# USI-WM-BN-BM-22-v1_0_0.net
KiCad netlist of a schematic drawn in EAGLE
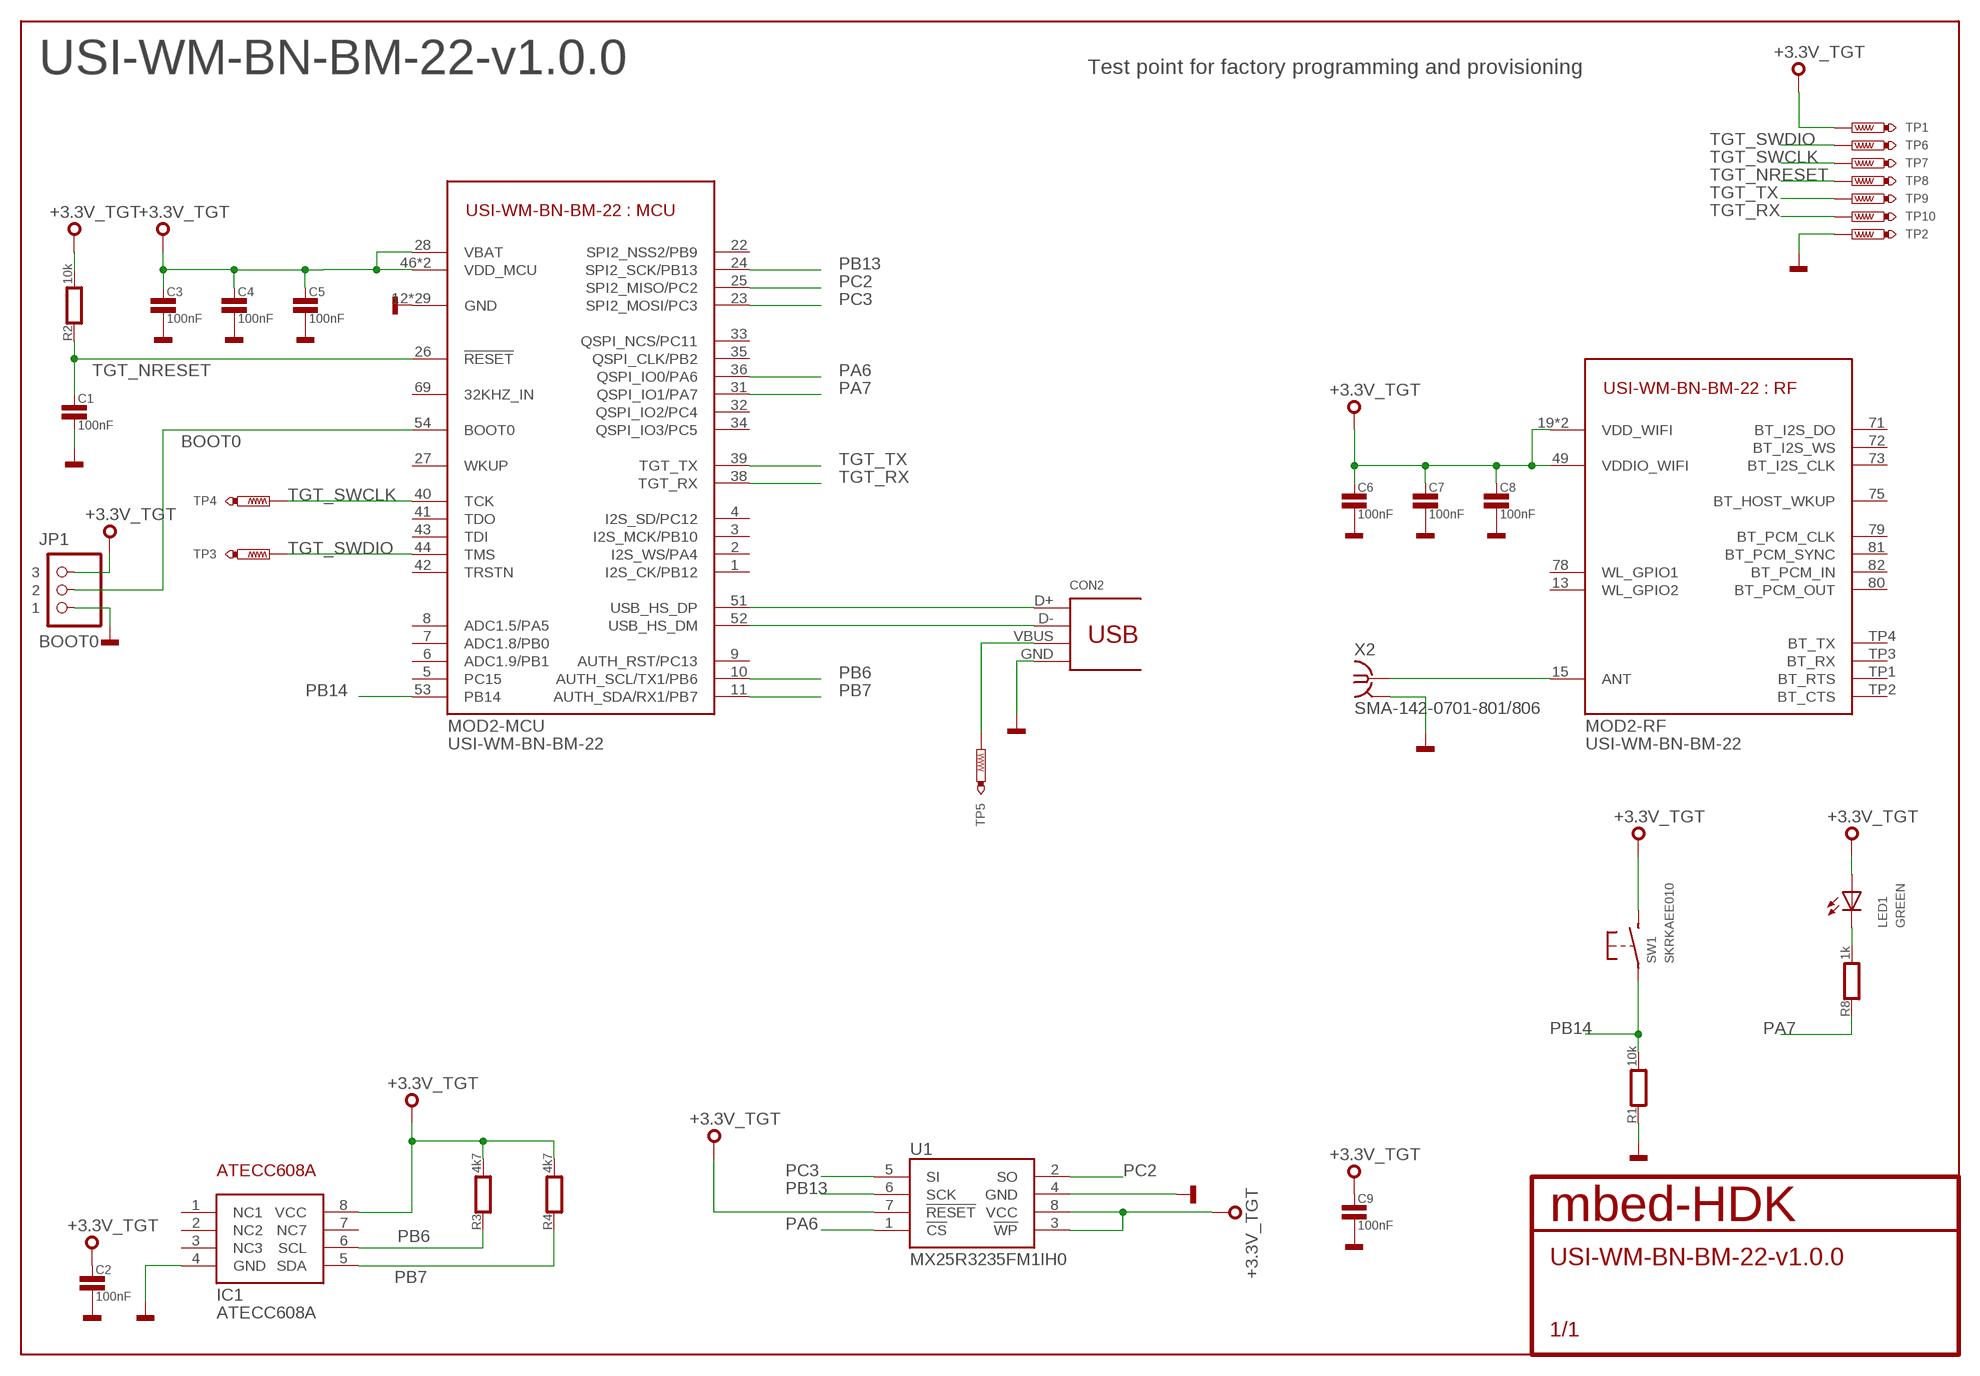
[diagram p0: schematic, sheet 1]

(export (version "E")
  (design (tool "Eeschema 10.0.6"))
  (components
    (comp (ref "C1")
      (value "100nF")
      (footprint "eagle-import:0603")
      (libsource (lib "eagle-import") (part "C0603"))
    )
    (comp (ref "C2")
      (value "100nF")
      (footprint "eagle-import:0603")
      (libsource (lib "eagle-import") (part "C0603"))
    )
    (comp (ref "C3")
      (value "100nF")
      (footprint "eagle-import:0603")
      (libsource (lib "eagle-import") (part "C0603"))
    )
    (comp (ref "C4")
      (value "100nF")
      (footprint "eagle-import:0603")
      (libsource (lib "eagle-import") (part "C0603"))
    )
    (comp (ref "C5")
      (value "100nF")
      (footprint "eagle-import:0603")
      (libsource (lib "eagle-import") (part "C0603"))
    )
    (comp (ref "C6")
      (value "100nF")
      (footprint "eagle-import:0603")
      (libsource (lib "eagle-import") (part "C0603"))
    )
    (comp (ref "C7")
      (value "100nF")
      (footprint "eagle-import:0603")
      (libsource (lib "eagle-import") (part "C0603"))
    )
    (comp (ref "C8")
      (value "100nF")
      (footprint "eagle-import:0603")
      (libsource (lib "eagle-import") (part "C0603"))
    )
    (comp (ref "C9")
      (value "100nF")
      (footprint "eagle-import:0603")
      (libsource (lib "eagle-import") (part "C0603"))
    )
    (comp (ref "CON2")
      (value "47346-0001")
      (footprint "eagle-import:USB-MICRO-B-H")
      (fields (field (name "MF") "MOLEX"))
      (libsource (lib "eagle-import") (part "47346-0001"))
    )
    (comp (ref "IC1")
      (value "ATECC608A")
      (footprint "eagle-import:SO8")
      (fields (field (name "MF") "Atmel"))
      (libsource (lib "eagle-import") (part "ATECC608A"))
    )
    (comp (ref "JP1")
      (value "BOOT0")
      (footprint "eagle-import:1X03")
      (libsource (lib "eagle-import") (part "PINHD-1X3"))
    )
    (comp (ref "LED1")
      (value "GREEN")
      (footprint "eagle-import:CHIPLED_0603")
      (fields (field (name "MF") "Wurth Electronics Inc"))
      (libsource (lib "eagle-import") (part "SMD_LED0603"))
    )
    (comp (ref "MOD2")
      (value "USI-WM-BN-BM-22")
      (footprint "eagle-import:USI-WM-BN-BM-22")
      (libsource (lib "eagle-import") (part "USI-WM-BN-BM-22"))
    )
    (comp (ref "R1")
      (value "10k")
      (footprint "eagle-import:0603")
      (libsource (lib "eagle-import") (part "R0603"))
    )
    (comp (ref "R2")
      (value "10k")
      (footprint "eagle-import:0603")
      (libsource (lib "eagle-import") (part "R0603"))
    )
    (comp (ref "R3")
      (value "4k7")
      (footprint "eagle-import:0603")
      (libsource (lib "eagle-import") (part "R0603"))
    )
    (comp (ref "R4")
      (value "4k7")
      (footprint "eagle-import:0603")
      (libsource (lib "eagle-import") (part "R0603"))
    )
    (comp (ref "R8")
      (value "1k")
      (footprint "eagle-import:0603")
      (libsource (lib "eagle-import") (part "R0603"))
    )
    (comp (ref "SW1")
      (value "SKRKAEE010")
      (footprint "eagle-import:SKRKAEE010")
      (fields (field (name "MF") "ALPS"))
      (libsource (lib "eagle-import") (part "SKRKAEE010"))
    )
    (comp (ref "TP1")
      (value "TEST_POINT-50R-SMD")
      (footprint "eagle-import:TP50-SMD")
      (libsource (lib "eagle-import") (part "TEST_POINT-50R-SMD"))
    )
    (comp (ref "TP2")
      (value "TEST_POINT-50R-SMD")
      (footprint "eagle-import:TP50-SMD")
      (libsource (lib "eagle-import") (part "TEST_POINT-50R-SMD"))
    )
    (comp (ref "TP3")
      (value "TEST_POINT-50R-SMD")
      (footprint "eagle-import:TP50-SMD")
      (libsource (lib "eagle-import") (part "TEST_POINT-50R-SMD"))
    )
    (comp (ref "TP4")
      (value "TEST_POINT-50R-SMD")
      (footprint "eagle-import:TP50-SMD")
      (libsource (lib "eagle-import") (part "TEST_POINT-50R-SMD"))
    )
    (comp (ref "TP5")
      (value "TEST_POINT-50R-SMD")
      (footprint "eagle-import:TP50-SMD")
      (libsource (lib "eagle-import") (part "TEST_POINT-50R-SMD"))
    )
    (comp (ref "TP6")
      (value "TEST_POINT-50R-SMD")
      (footprint "eagle-import:TP50-SMD")
      (libsource (lib "eagle-import") (part "TEST_POINT-50R-SMD"))
    )
    (comp (ref "TP7")
      (value "TEST_POINT-50R-SMD")
      (footprint "eagle-import:TP50-SMD")
      (libsource (lib "eagle-import") (part "TEST_POINT-50R-SMD"))
    )
    (comp (ref "TP8")
      (value "TEST_POINT-50R-SMD")
      (footprint "eagle-import:TP50-SMD")
      (libsource (lib "eagle-import") (part "TEST_POINT-50R-SMD"))
    )
    (comp (ref "TP9")
      (value "TEST_POINT-50R-SMD")
      (footprint "eagle-import:TP50-SMD")
      (libsource (lib "eagle-import") (part "TEST_POINT-50R-SMD"))
    )
    (comp (ref "TP10")
      (value "TEST_POINT-50R-SMD")
      (footprint "eagle-import:TP50-SMD")
      (libsource (lib "eagle-import") (part "TEST_POINT-50R-SMD"))
    )
    (comp (ref "U1")
      (value "MX25R3235FM1IH0")
      (footprint "eagle-import:SO8")
      (fields (field (name "MF") "Macronix"))
      (libsource (lib "eagle-import") (part "MX25R3235FM1IH0"))
    )
    (comp (ref "X2")
      (value "SMA-142-0701-801/806")
      (footprint "eagle-import:J502-ND-142-0701-801_806")
      (fields (field (name "MF") "JOHNSON COMPONENTS") (field (name "MPN") "142-0701-801"))
      (libsource (lib "eagle-import") (part "SMA-142-0701-801/806"))
    )
  )
  (nets
    (net (code "1") (name "+3.3V_TGT") (class "Default")
      (node (ref "C2") (pin "1") (pinfunction "P$1_1") (pintype "passive"))
      (node (ref "C3") (pin "1") (pinfunction "P$1_1") (pintype "passive"))
      (node (ref "C4") (pin "1") (pinfunction "P$1_1") (pintype "passive"))
      (node (ref "C5") (pin "1") (pinfunction "P$1_1") (pintype "passive"))
      (node (ref "C6") (pin "1") (pinfunction "P$1_1") (pintype "passive"))
      (node (ref "C7") (pin "1") (pinfunction "P$1_1") (pintype "passive"))
      (node (ref "C8") (pin "1") (pinfunction "P$1_1") (pintype "passive"))
      (node (ref "C9") (pin "1") (pinfunction "P$1_1") (pintype "passive"))
      (node (ref "IC1") (pin "8") (pinfunction "VCC_8") (pintype "bidirectional"))
      (node (ref "JP1") (pin "3") (pinfunction "3_3") (pintype "passive"))
      (node (ref "LED1") (pin "A") (pinfunction "A_A") (pintype "passive"))
      (node (ref "MOD2") (pin "19") (pinfunction "VDD_WIFI_19") (pintype "bidirectional"))
      (node (ref "MOD2") (pin "20") (pinfunction "VDD_WIFI_20") (pintype "bidirectional"))
      (node (ref "MOD2") (pin "28") (pinfunction "VBAT_28") (pintype "bidirectional"))
      (node (ref "MOD2") (pin "46") (pinfunction "VDD_MCU_46") (pintype "bidirectional"))
      (node (ref "MOD2") (pin "47") (pinfunction "VDD_MCU_47") (pintype "bidirectional"))
      (node (ref "MOD2") (pin "49") (pinfunction "VDDIO_WIFI_49") (pintype "bidirectional"))
      (node (ref "R2") (pin "2") (pinfunction "P$2_2") (pintype "passive"))
      (node (ref "R3") (pin "2") (pinfunction "P$2_2") (pintype "passive"))
      (node (ref "R4") (pin "2") (pinfunction "P$2_2") (pintype "passive"))
      (node (ref "SW1") (pin "P$2") (pinfunction "S_P$2") (pintype "passive"))
      (node (ref "TP1") (pin "TP") (pinfunction "TP_TP") (pintype "input"))
      (node (ref "U1") (pin "3") (pinfunction "~{WP}_3") (pintype "bidirectional"))
      (node (ref "U1") (pin "7") (pinfunction "~{RESET}_7") (pintype "bidirectional"))
      (node (ref "U1") (pin "8") (pinfunction "VCC_8") (pintype "bidirectional"))
    )
    (net (code "2") (name "/BOOT0") (class "Default")
      (node (ref "JP1") (pin "2") (pinfunction "2_2") (pintype "passive"))
      (node (ref "MOD2") (pin "54") (pinfunction "BOOT0_54") (pintype "bidirectional"))
    )
    (net (code "3") (name "/PA6") (class "Default")
      (node (ref "MOD2") (pin "36") (pinfunction "QSPI_IO0/PA6_36") (pintype "bidirectional"))
      (node (ref "U1") (pin "1") (pinfunction "~{CS}_1") (pintype "bidirectional"))
    )
    (net (code "4") (name "/PA7") (class "Default")
      (node (ref "MOD2") (pin "31") (pinfunction "QSPI_IO1/PA7_31") (pintype "bidirectional"))
      (node (ref "R8") (pin "1") (pinfunction "P$1_1") (pintype "passive"))
    )
    (net (code "5") (name "/PB6") (class "Default")
      (node (ref "IC1") (pin "6") (pinfunction "SCL_6") (pintype "bidirectional"))
      (node (ref "MOD2") (pin "10") (pinfunction "AUTH_SCL/TX1/PB6_10") (pintype "bidirectional"))
      (node (ref "R3") (pin "1") (pinfunction "P$1_1") (pintype "passive"))
    )
    (net (code "6") (name "/PB7") (class "Default")
      (node (ref "IC1") (pin "5") (pinfunction "SDA_5") (pintype "bidirectional"))
      (node (ref "MOD2") (pin "11") (pinfunction "AUTH_SDA/RX1/PB7_11") (pintype "bidirectional"))
      (node (ref "R4") (pin "1") (pinfunction "P$1_1") (pintype "passive"))
    )
    (net (code "7") (name "/PB13") (class "Default")
      (node (ref "MOD2") (pin "24") (pinfunction "SPI2_SCK/PB13_24") (pintype "bidirectional"))
      (node (ref "U1") (pin "6") (pinfunction "SCK_6") (pintype "bidirectional"))
    )
    (net (code "8") (name "/PB14") (class "Default")
      (node (ref "MOD2") (pin "53") (pinfunction "PB14_53") (pintype "bidirectional"))
      (node (ref "R1") (pin "2") (pinfunction "P$2_2") (pintype "passive"))
      (node (ref "SW1") (pin "P$1") (pinfunction "P_P$1") (pintype "passive"))
    )
    (net (code "9") (name "/PC2") (class "Default")
      (node (ref "MOD2") (pin "25") (pinfunction "SPI2_MISO/PC2_25") (pintype "bidirectional"))
      (node (ref "U1") (pin "2") (pinfunction "SO_2") (pintype "bidirectional"))
    )
    (net (code "10") (name "/PC3") (class "Default")
      (node (ref "MOD2") (pin "23") (pinfunction "SPI2_MOSI/PC3_23") (pintype "bidirectional"))
      (node (ref "U1") (pin "5") (pinfunction "SI_5") (pintype "bidirectional"))
    )
    (net (code "11") (name "/TGT_NRESET") (class "Default")
      (node (ref "C1") (pin "1") (pinfunction "P$1_1") (pintype "passive"))
      (node (ref "MOD2") (pin "26") (pinfunction "~{RESET}_26") (pintype "bidirectional"))
      (node (ref "R2") (pin "1") (pinfunction "P$1_1") (pintype "passive"))
      (node (ref "TP8") (pin "TP") (pinfunction "TP_TP") (pintype "input"))
    )
    (net (code "12") (name "/TGT_RX") (class "Default")
      (node (ref "MOD2") (pin "38") (pinfunction "TGT_RX_38") (pintype "bidirectional"))
      (node (ref "TP10") (pin "TP") (pinfunction "TP_TP") (pintype "input"))
    )
    (net (code "13") (name "/TGT_SWCLK") (class "Default")
      (node (ref "MOD2") (pin "40") (pinfunction "TCK_40") (pintype "bidirectional"))
      (node (ref "TP4") (pin "TP") (pinfunction "TP_TP") (pintype "input"))
      (node (ref "TP7") (pin "TP") (pinfunction "TP_TP") (pintype "input"))
    )
    (net (code "14") (name "/TGT_SWDIO") (class "Default")
      (node (ref "MOD2") (pin "44") (pinfunction "TMS_44") (pintype "bidirectional"))
      (node (ref "TP3") (pin "TP") (pinfunction "TP_TP") (pintype "input"))
      (node (ref "TP6") (pin "TP") (pinfunction "TP_TP") (pintype "input"))
    )
    (net (code "15") (name "/TGT_TX") (class "Default")
      (node (ref "MOD2") (pin "39") (pinfunction "TGT_TX_39") (pintype "bidirectional"))
      (node (ref "TP9") (pin "TP") (pinfunction "TP_TP") (pintype "input"))
    )
    (net (code "16") (name "GND") (class "Default")
      (node (ref "C1") (pin "2") (pinfunction "P$2_2") (pintype "passive"))
      (node (ref "C2") (pin "2") (pinfunction "P$2_2") (pintype "passive"))
      (node (ref "C3") (pin "2") (pinfunction "P$2_2") (pintype "passive"))
      (node (ref "C4") (pin "2") (pinfunction "P$2_2") (pintype "passive"))
      (node (ref "C5") (pin "2") (pinfunction "P$2_2") (pintype "passive"))
      (node (ref "C6") (pin "2") (pinfunction "P$2_2") (pintype "passive"))
      (node (ref "C7") (pin "2") (pinfunction "P$2_2") (pintype "passive"))
      (node (ref "C8") (pin "2") (pinfunction "P$2_2") (pintype "passive"))
      (node (ref "C9") (pin "2") (pinfunction "P$2_2") (pintype "passive"))
      (node (ref "CON2") (pin "GND") (pinfunction "GND_GND") (pintype "bidirectional"))
      (node (ref "IC1") (pin "4") (pinfunction "GND_4") (pintype "bidirectional"))
      (node (ref "JP1") (pin "1") (pinfunction "1_1") (pintype "passive"))
      (node (ref "MOD2") (pin "12") (pinfunction "GND_12") (pintype "bidirectional"))
      (node (ref "MOD2") (pin "14") (pinfunction "GND_14") (pintype "bidirectional"))
      (node (ref "MOD2") (pin "16") (pinfunction "GND_16") (pintype "bidirectional"))
      (node (ref "MOD2") (pin "17") (pinfunction "GND_17") (pintype "bidirectional"))
      (node (ref "MOD2") (pin "18") (pinfunction "GND_18") (pintype "bidirectional"))
      (node (ref "MOD2") (pin "21") (pinfunction "GND_21") (pintype "bidirectional"))
      (node (ref "MOD2") (pin "29") (pinfunction "GND_29") (pintype "bidirectional"))
      (node (ref "MOD2") (pin "30") (pinfunction "GND_30") (pintype "bidirectional"))
      (node (ref "MOD2") (pin "37") (pinfunction "GND_37") (pintype "bidirectional"))
      (node (ref "MOD2") (pin "45") (pinfunction "GND_45") (pintype "bidirectional"))
      (node (ref "MOD2") (pin "48") (pinfunction "GND_48") (pintype "bidirectional"))
      (node (ref "MOD2") (pin "50") (pinfunction "GND_50") (pintype "bidirectional"))
      (node (ref "MOD2") (pin "55") (pinfunction "GND_55") (pintype "bidirectional"))
      (node (ref "MOD2") (pin "56") (pinfunction "GND_56") (pintype "bidirectional"))
      (node (ref "MOD2") (pin "57") (pinfunction "GND_57") (pintype "bidirectional"))
      (node (ref "MOD2") (pin "58") (pinfunction "GND_58") (pintype "bidirectional"))
      (node (ref "MOD2") (pin "59") (pinfunction "GND_59") (pintype "bidirectional"))
      (node (ref "MOD2") (pin "60") (pinfunction "GND_60") (pintype "bidirectional"))
      (node (ref "MOD2") (pin "61") (pinfunction "GND_61") (pintype "bidirectional"))
      (node (ref "MOD2") (pin "62") (pinfunction "GND_62") (pintype "bidirectional"))
      (node (ref "MOD2") (pin "63") (pinfunction "GND_63") (pintype "bidirectional"))
      (node (ref "MOD2") (pin "64") (pinfunction "GND_64") (pintype "bidirectional"))
      (node (ref "MOD2") (pin "65") (pinfunction "GND_65") (pintype "bidirectional"))
      (node (ref "MOD2") (pin "66") (pinfunction "GND_66") (pintype "bidirectional"))
      (node (ref "MOD2") (pin "67") (pinfunction "GND_67") (pintype "bidirectional"))
      (node (ref "MOD2") (pin "68") (pinfunction "GND_68") (pintype "bidirectional"))
      (node (ref "MOD2") (pin "70") (pinfunction "GND_70") (pintype "bidirectional"))
      (node (ref "MOD2") (pin "74") (pinfunction "GND_74") (pintype "bidirectional"))
      (node (ref "MOD2") (pin "83") (pinfunction "GND_83") (pintype "bidirectional"))
      (node (ref "R1") (pin "1") (pinfunction "P$1_1") (pintype "passive"))
      (node (ref "TP2") (pin "TP") (pinfunction "TP_TP") (pintype "input"))
      (node (ref "U1") (pin "4") (pinfunction "GND_4") (pintype "bidirectional"))
      (node (ref "X2") (pin "G@1") (pinfunction "2_G@1") (pintype "passive"))
      (node (ref "X2") (pin "G@2") (pinfunction "2_G@2") (pintype "passive"))
      (node (ref "X2") (pin "G@3") (pinfunction "2_G@3") (pintype "passive"))
      (node (ref "X2") (pin "G@4") (pinfunction "2_G@4") (pintype "passive"))
    )
    (net (code "17") (name "Net-(CON2-PadVBUS)") (class "Default")
      (node (ref "CON2") (pin "VBUS") (pinfunction "VBUS_VBUS") (pintype "bidirectional"))
      (node (ref "TP5") (pin "TP") (pinfunction "TP_TP") (pintype "input"))
    )
    (net (code "18") (name "Net-(MOD2A-USB_HS_DM)") (class "Default")
      (node (ref "CON2") (pin "D-") (pinfunction "D-_D-") (pintype "bidirectional"))
      (node (ref "MOD2") (pin "52") (pinfunction "USB_HS_DM_52") (pintype "bidirectional"))
    )
    (net (code "19") (name "Net-(MOD2A-USB_HS_DP)") (class "Default")
      (node (ref "CON2") (pin "D+") (pinfunction "D+_D+") (pintype "bidirectional"))
      (node (ref "MOD2") (pin "51") (pinfunction "USB_HS_DP_51") (pintype "bidirectional"))
    )
    (net (code "20") (name "Net-(MOD2B-ANT)") (class "Default")
      (node (ref "MOD2") (pin "15") (pinfunction "ANT_15") (pintype "bidirectional"))
      (node (ref "X2") (pin "1") (pinfunction "1_1") (pintype "passive"))
    )
    (net (code "21") (name "Net-(R8-P$2)") (class "Default")
      (node (ref "LED1") (pin "C") (pinfunction "C_C") (pintype "passive"))
      (node (ref "R8") (pin "2") (pinfunction "P$2_2") (pintype "passive"))
    )
    (net (code "22") (name "unconnected-(IC1-NC1-Pad1)") (class "Default")
      (node (ref "IC1") (pin "1") (pinfunction "NC1_1") (pintype "bidirectional"))
    )
    (net (code "23") (name "unconnected-(IC1-NC2-Pad2)") (class "Default")
      (node (ref "IC1") (pin "2") (pinfunction "NC2_2") (pintype "bidirectional"))
    )
    (net (code "24") (name "unconnected-(IC1-NC3-Pad3)") (class "Default")
      (node (ref "IC1") (pin "3") (pinfunction "NC3_3") (pintype "bidirectional"))
    )
    (net (code "25") (name "unconnected-(IC1-NC7-Pad7)") (class "Default")
      (node (ref "IC1") (pin "7") (pinfunction "NC7_7") (pintype "bidirectional"))
    )
    (net (code "26") (name "unconnected-(MOD2A-32KHZ_IN-Pad69)") (class "Default")
      (node (ref "MOD2") (pin "69") (pinfunction "32KHZ_IN_69") (pintype "bidirectional"))
    )
    (net (code "27") (name "unconnected-(MOD2A-ADC1.5{slash}PA5-Pad8)") (class "Default")
      (node (ref "MOD2") (pin "8") (pinfunction "ADC1.5/PA5_8") (pintype "bidirectional"))
    )
    (net (code "28") (name "unconnected-(MOD2A-ADC1.8{slash}PB0-Pad7)") (class "Default")
      (node (ref "MOD2") (pin "7") (pinfunction "ADC1.8/PB0_7") (pintype "bidirectional"))
    )
    (net (code "29") (name "unconnected-(MOD2A-ADC1.9{slash}PB1-Pad6)") (class "Default")
      (node (ref "MOD2") (pin "6") (pinfunction "ADC1.9/PB1_6") (pintype "bidirectional"))
    )
    (net (code "30") (name "unconnected-(MOD2A-AUTH_RST{slash}PC13-Pad9)") (class "Default")
      (node (ref "MOD2") (pin "9") (pinfunction "AUTH_RST/PC13_9") (pintype "bidirectional"))
    )
    (net (code "31") (name "unconnected-(MOD2A-I2S_CK{slash}PB12-Pad1)") (class "Default")
      (node (ref "MOD2") (pin "1") (pinfunction "I2S_CK/PB12_1") (pintype "bidirectional"))
    )
    (net (code "32") (name "unconnected-(MOD2A-I2S_MCK{slash}PB10-Pad3)") (class "Default")
      (node (ref "MOD2") (pin "3") (pinfunction "I2S_MCK/PB10_3") (pintype "bidirectional"))
    )
    (net (code "33") (name "unconnected-(MOD2A-I2S_SD{slash}PC12-Pad4)") (class "Default")
      (node (ref "MOD2") (pin "4") (pinfunction "I2S_SD/PC12_4") (pintype "bidirectional"))
    )
    (net (code "34") (name "unconnected-(MOD2A-I2S_WS{slash}PA4-Pad2)") (class "Default")
      (node (ref "MOD2") (pin "2") (pinfunction "I2S_WS/PA4_2") (pintype "bidirectional"))
    )
    (net (code "35") (name "unconnected-(MOD2A-PC15-Pad5)") (class "Default")
      (node (ref "MOD2") (pin "5") (pinfunction "PC15_5") (pintype "bidirectional"))
    )
    (net (code "36") (name "unconnected-(MOD2A-QSPI_CLK{slash}PB2-Pad35)") (class "Default")
      (node (ref "MOD2") (pin "35") (pinfunction "QSPI_CLK/PB2_35") (pintype "bidirectional"))
    )
    (net (code "37") (name "unconnected-(MOD2A-QSPI_IO2{slash}PC4-Pad32)") (class "Default")
      (node (ref "MOD2") (pin "32") (pinfunction "QSPI_IO2/PC4_32") (pintype "bidirectional"))
    )
    (net (code "38") (name "unconnected-(MOD2A-QSPI_IO3{slash}PC5-Pad34)") (class "Default")
      (node (ref "MOD2") (pin "34") (pinfunction "QSPI_IO3/PC5_34") (pintype "bidirectional"))
    )
    (net (code "39") (name "unconnected-(MOD2A-QSPI_NCS{slash}PC11-Pad33)") (class "Default")
      (node (ref "MOD2") (pin "33") (pinfunction "QSPI_NCS/PC11_33") (pintype "bidirectional"))
    )
    (net (code "40") (name "unconnected-(MOD2A-SPI2_NSS2{slash}PB9-Pad22)") (class "Default")
      (node (ref "MOD2") (pin "22") (pinfunction "SPI2_NSS2/PB9_22") (pintype "bidirectional"))
    )
    (net (code "41") (name "unconnected-(MOD2A-TDI-Pad43)") (class "Default")
      (node (ref "MOD2") (pin "43") (pinfunction "TDI_43") (pintype "bidirectional"))
    )
    (net (code "42") (name "unconnected-(MOD2A-TDO-Pad41)") (class "Default")
      (node (ref "MOD2") (pin "41") (pinfunction "TDO_41") (pintype "bidirectional"))
    )
    (net (code "43") (name "unconnected-(MOD2A-TRSTN-Pad42)") (class "Default")
      (node (ref "MOD2") (pin "42") (pinfunction "TRSTN_42") (pintype "bidirectional"))
    )
    (net (code "44") (name "unconnected-(MOD2A-WKUP-Pad27)") (class "Default")
      (node (ref "MOD2") (pin "27") (pinfunction "WKUP_27") (pintype "bidirectional"))
    )
    (net (code "45") (name "unconnected-(MOD2B-BT_CTS-PadTP2)") (class "Default")
      (node (ref "MOD2") (pin "TP2") (pinfunction "BT_CTS_TP2") (pintype "bidirectional"))
    )
    (net (code "46") (name "unconnected-(MOD2B-BT_HOST_WKUP-Pad75)") (class "Default")
      (node (ref "MOD2") (pin "75") (pinfunction "BT_HOST_WKUP_75") (pintype "bidirectional"))
    )
    (net (code "47") (name "unconnected-(MOD2B-BT_I2S_CLK-Pad73)") (class "Default")
      (node (ref "MOD2") (pin "73") (pinfunction "BT_I2S_CLK_73") (pintype "bidirectional"))
    )
    (net (code "48") (name "unconnected-(MOD2B-BT_I2S_DO-Pad71)") (class "Default")
      (node (ref "MOD2") (pin "71") (pinfunction "BT_I2S_DO_71") (pintype "bidirectional"))
    )
    (net (code "49") (name "unconnected-(MOD2B-BT_I2S_WS-Pad72)") (class "Default")
      (node (ref "MOD2") (pin "72") (pinfunction "BT_I2S_WS_72") (pintype "bidirectional"))
    )
    (net (code "50") (name "unconnected-(MOD2B-BT_PCM_CLK-Pad79)") (class "Default")
      (node (ref "MOD2") (pin "79") (pinfunction "BT_PCM_CLK_79") (pintype "bidirectional"))
    )
    (net (code "51") (name "unconnected-(MOD2B-BT_PCM_IN-Pad82)") (class "Default")
      (node (ref "MOD2") (pin "82") (pinfunction "BT_PCM_IN_82") (pintype "bidirectional"))
    )
    (net (code "52") (name "unconnected-(MOD2B-BT_PCM_OUT-Pad80)") (class "Default")
      (node (ref "MOD2") (pin "80") (pinfunction "BT_PCM_OUT_80") (pintype "bidirectional"))
    )
    (net (code "53") (name "unconnected-(MOD2B-BT_PCM_SYNC-Pad81)") (class "Default")
      (node (ref "MOD2") (pin "81") (pinfunction "BT_PCM_SYNC_81") (pintype "bidirectional"))
    )
    (net (code "54") (name "unconnected-(MOD2B-BT_RTS-PadTP1)") (class "Default")
      (node (ref "MOD2") (pin "TP1") (pinfunction "BT_RTS_TP1") (pintype "bidirectional"))
    )
    (net (code "55") (name "unconnected-(MOD2B-BT_RX-PadTP3)") (class "Default")
      (node (ref "MOD2") (pin "TP3") (pinfunction "BT_RX_TP3") (pintype "bidirectional"))
    )
    (net (code "56") (name "unconnected-(MOD2B-BT_TX-PadTP4)") (class "Default")
      (node (ref "MOD2") (pin "TP4") (pinfunction "BT_TX_TP4") (pintype "bidirectional"))
    )
    (net (code "57") (name "unconnected-(MOD2B-WL_GPIO1-Pad78)") (class "Default")
      (node (ref "MOD2") (pin "78") (pinfunction "WL_GPIO1_78") (pintype "bidirectional"))
    )
    (net (code "58") (name "unconnected-(MOD2B-WL_GPIO2-Pad13)") (class "Default")
      (node (ref "MOD2") (pin "13") (pinfunction "WL_GPIO2_13") (pintype "bidirectional"))
    )
  )
)
